# pc2micro.net
KiCad netlist of a schematic drawn in Altium Designer
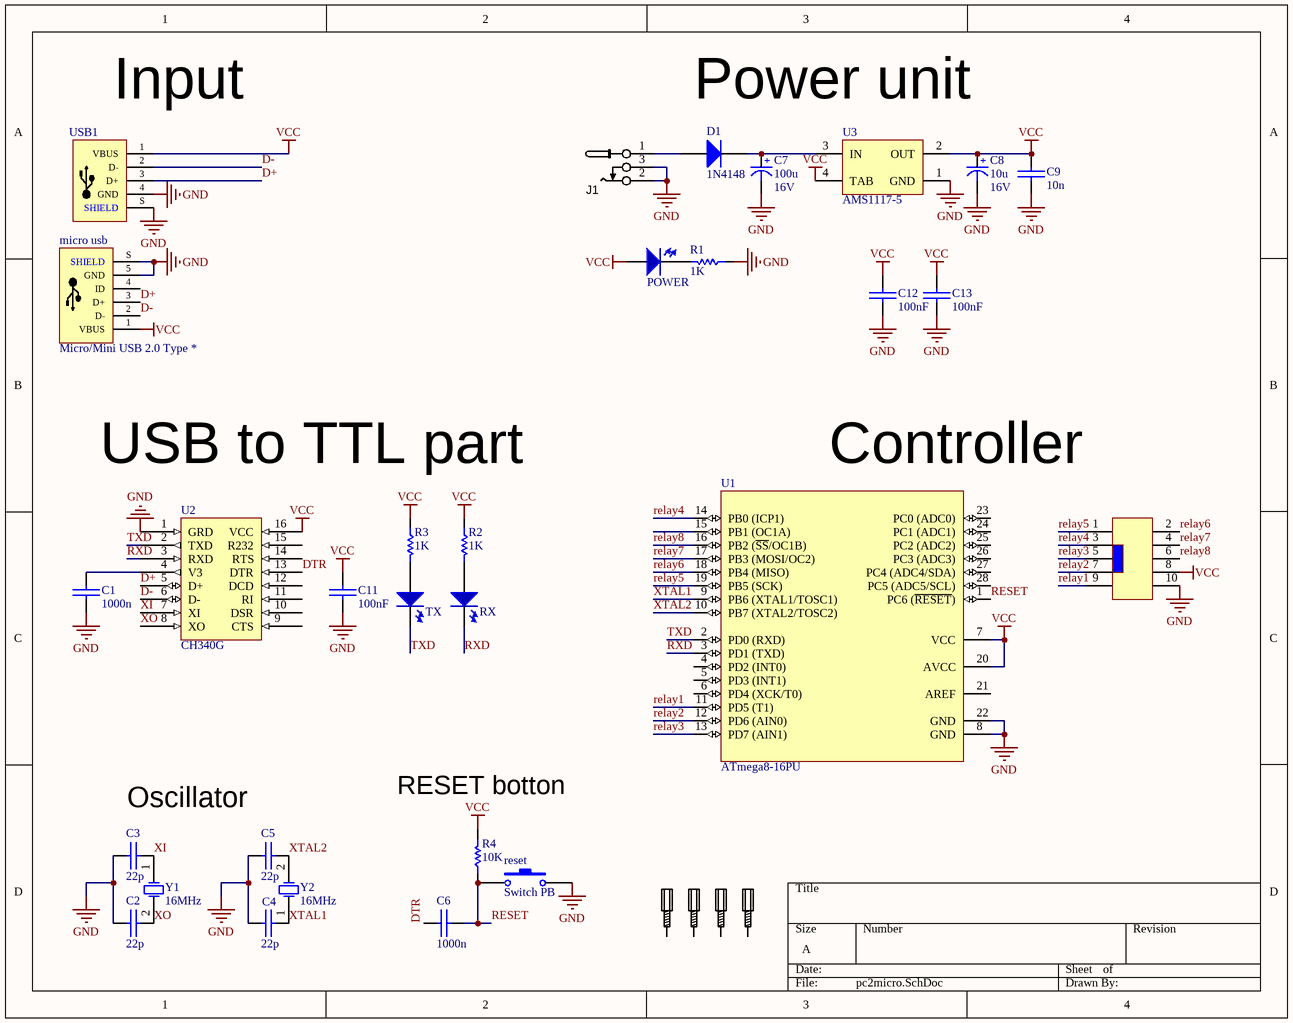
[diagram p0: pc2micro.SchDoc]

(export (version "E")
  (design (tool "Eeschema 10.0.6"))
  (components
    (comp (ref "C1")
      (value "1000n")
      (footprint "Cap - 100nF")
      (description "Bipolar Capacitor")
      (fields (field (name "VOLTAGE") "100V") (field (name "DESIGNER") "Saeid Jorablo"))
      (libsource (lib "My Library") (part "Cap-Bipolar"))
    )
    (comp (ref "C2")
      (value "22p")
      (footprint "Cap - 100nF")
      (description "Bipolar Capacitor")
      (fields (field (name "VOLTAGE") "100V") (field (name "DESIGNER") "Saeid Jorablo"))
      (libsource (lib "My Library") (part "Cap-Bipolar"))
    )
    (comp (ref "C3")
      (value "22p")
      (footprint "Cap - 100nF")
      (description "Bipolar Capacitor")
      (fields (field (name "VOLTAGE") "100V") (field (name "DESIGNER") "Saeid Jorablo"))
      (libsource (lib "My Library") (part "Cap-Bipolar"))
    )
    (comp (ref "C4")
      (value "22p")
      (footprint "Cap - 100nF")
      (description "Bipolar Capacitor")
      (fields (field (name "VOLTAGE") "100V") (field (name "DESIGNER") "Saeid Jorablo"))
      (libsource (lib "My Library") (part "Cap-Bipolar"))
    )
    (comp (ref "C5")
      (value "22p")
      (footprint "Cap - 100nF")
      (description "Bipolar Capacitor")
      (fields (field (name "VOLTAGE") "100V") (field (name "DESIGNER") "Saeid Jorablo"))
      (libsource (lib "My Library") (part "Cap-Bipolar"))
    )
    (comp (ref "C6")
      (value "1000n")
      (footprint "Cap - 100nF")
      (description "Bipolar Capacitor")
      (fields (field (name "VOLTAGE") "100V") (field (name "DESIGNER") "Saeid Jorablo"))
      (libsource (lib "My Library") (part "Cap-Bipolar"))
    )
    (comp (ref "C7")
      (value "100u")
      (footprint "cap 01")
      (description "Polar Capacitor")
      (fields (field (name "VOLTAGE") "16V") (field (name "DESIGNER") "Saeid Jorablo"))
      (libsource (lib "My Library") (part "Cap-Polar"))
    )
    (comp (ref "C8")
      (value "10u")
      (footprint "cap 01")
      (description "Polar Capacitor")
      (fields (field (name "VOLTAGE") "16V") (field (name "DESIGNER") "Saeid Jorablo"))
      (libsource (lib "My Library") (part "Cap-Polar"))
    )
    (comp (ref "C9")
      (value "10n")
      (footprint "Cap - 100nF")
      (description "Bipolar Capacitor")
      (fields (field (name "VOLTAGE") "100V") (field (name "DESIGNER") "Saeid Jorablo"))
      (libsource (lib "My Library") (part "Cap-Bipolar"))
    )
    (comp (ref "C11")
      (value "100nF")
      (footprint "Cap - 100nF")
      (description "Bipolar Capacitor")
      (fields (field (name "VOLTAGE") "100V") (field (name "DESIGNER") "Saeid Jorablo"))
      (libsource (lib "My Library") (part "Cap-Bipolar"))
    )
    (comp (ref "C12")
      (value "100nF")
      (footprint "Cap - 100nF")
      (description "Bipolar Capacitor")
      (fields (field (name "VOLTAGE") "100V") (field (name "DESIGNER") "Saeid Jorablo"))
      (libsource (lib "My Library") (part "Cap-Bipolar"))
    )
    (comp (ref "C13")
      (value "100nF")
      (footprint "Cap - 100nF")
      (description "Bipolar Capacitor")
      (fields (field (name "VOLTAGE") "100V") (field (name "DESIGNER") "Saeid Jorablo"))
      (libsource (lib "My Library") (part "Cap-Bipolar"))
    )
    (comp (ref "D1")
      (value "1N4148")
      (footprint "DO-35")
      (description "High Conductance Fast Diode")
      (fields (field (name "PUBLISHER") "Altium Limited"))
      (libsource (lib "My Library") (part "Diode 1N4148"))
    )
    (comp (ref "IDC1")
      (value "DC3-10")
      (footprint "DC3-2.54-10")
      (description "简易牛角座, 10pins")
      (libsource (lib "AD_Connectors") (part "DC3-10"))
    )
    (comp (ref "J1")
      (value "CONN_PWR_JACK_2.1x5.5mm")
      (footprint "CONN_PWR_JACK_v2")
      (description "Power Connector, THT, 2.1mm ID, 5.5mm OD")
      (fields (field (name "MANUFACTURER") "CUI Inc."))
      (libsource (lib "LimeNet-Micro_2v0") (part "CONN_PWR_JACK_2.1x5.5mm"))
    )
    (comp (ref "MECH1")
      (value "# pcs.")
      (footprint "PCB_standoff")
      (description "STANDOFF M/F MET 5MM HEX 10MM L")
      (fields (field (name "MANUFACTURER") "FIX&FASTEN"))
      (libsource (lib "LimeNet-Micro_2v0") (part "STANDOFF_M-F_THREADED_M3x8x10mm_HEX_5mm dia"))
    )
    (comp (ref "MECH2")
      (value "# pcs.")
      (footprint "PCB_standoff")
      (description "STANDOFF M/F MET 5MM HEX 10MM L")
      (fields (field (name "MANUFACTURER") "FIX&FASTEN"))
      (libsource (lib "LimeNet-Micro_2v0") (part "STANDOFF_M-F_THREADED_M3x8x10mm_HEX_5mm dia"))
    )
    (comp (ref "MECH3")
      (value "# pcs.")
      (footprint "PCB_standoff")
      (description "STANDOFF M/F MET 5MM HEX 10MM L")
      (fields (field (name "MANUFACTURER") "FIX&FASTEN"))
      (libsource (lib "LimeNet-Micro_2v0") (part "STANDOFF_M-F_THREADED_M3x8x10mm_HEX_5mm dia"))
    )
    (comp (ref "MECH4")
      (value "# pcs.")
      (footprint "PCB_standoff")
      (description "STANDOFF M/F MET 5MM HEX 10MM L")
      (fields (field (name "MANUFACTURER") "FIX&FASTEN"))
      (libsource (lib "LimeNet-Micro_2v0") (part "STANDOFF_M-F_THREADED_M3x8x10mm_HEX_5mm dia"))
    )
    (comp (ref "micro usb")
      (value "Micro/Mini USB 2.0 Type *")
      (footprint "Micro_USB2_0_B_SMT_DIP2_1")
      (description "Micro and Mini USB 2.0 (Type A and Type A/B)")
      (libsource (lib "AD_Connectors") (part "USB2_0-Micro&Mini"))
    )
    (comp (ref "POWER")
      (value "SMD LED")
      (footprint "LED 5mm")
      (libsource (lib "ZetaBoard_Lib") (part "LED SMD"))
    )
    (comp (ref "R1")
      (value "1K")
      (footprint "Res-(1/4)")
      (description "Resistor")
      (fields (field (name "TOLERANCE") "5%") (field (name "POWER") "1/8 W"))
      (libsource (lib "My Library") (part "Resistor"))
    )
    (comp (ref "R2")
      (value "1K")
      (footprint "Res-(1/4)")
      (description "Resistor")
      (fields (field (name "TOLERANCE") "5%") (field (name "POWER") "1/8 W"))
      (libsource (lib "My Library") (part "Resistor"))
    )
    (comp (ref "R3")
      (value "1K")
      (footprint "Res-(1/4)")
      (description "Resistor")
      (fields (field (name "TOLERANCE") "5%") (field (name "POWER") "1/8 W"))
      (libsource (lib "My Library") (part "Resistor"))
    )
    (comp (ref "R4")
      (value "10K")
      (footprint "Res-(1/4)")
      (description "Resistor")
      (fields (field (name "TOLERANCE") "5%") (field (name "POWER") "1/8 W"))
      (libsource (lib "My Library") (part "Resistor"))
    )
    (comp (ref "reset")
      (value "Switch PB")
      (footprint "Switch - Push to On")
      (description "Push Button Switch")
      (libsource (lib "My Library") (part "Switch PB"))
    )
    (comp (ref "RX")
      (value "SMD LED")
      (footprint "LED 5mm")
      (libsource (lib "ZetaBoard_Lib") (part "LED SMD"))
    )
    (comp (ref "TX")
      (value "SMD LED")
      (footprint "LED 5mm")
      (libsource (lib "ZetaBoard_Lib") (part "LED SMD"))
    )
    (comp (ref "U1")
      (value "ATmega8-16PU")
      (footprint "28P3")
      (libsource (lib "Atmel Microcontroller megaAVR") (part "ATmega8-16PU"))
    )
    (comp (ref "U2") (value "CH340G") (footprint "SOP-16") (libsource (lib "CH340.Schlib1") (part "CH340G")))
    (comp (ref "U3")
      (value "AMS1117-5")
      (footprint "MP04A_N")
      (description "x.x Volt, 800mA Low-Dropout Linear Regulator, 4-pin SOT-223")
      (fields
        (field (name "PARTNUMBER") "LM1117IMP-3.3")
        (field (name "MANUFACTURER") "National Semiconductor")
        (field (name "PUBLISHER") "Altium Limited")
      )
      (libsource (lib "My Library") (part "LM1117IMP-x.x"))
    )
    (comp (ref "USB1")
      (value "USB 2.0 Type *")
      (footprint "USB2_0_A_DIP")
      (description "USB 2.0 Type A and Type B")
      (fields (field (name "PART NUMBER") "61400413321") (field (name "PUBLISHER") "Wurth Elektronik"))
      (libsource (lib "AD_Connectors") (part "USB2_0-A&B"))
    )
    (comp (ref "Y1")
      (value "16MHz")
      (footprint "XTAL Small")
      (description "XTAL Crystal")
      (libsource (lib "My Library") (part "XTAL"))
    )
    (comp (ref "Y2")
      (value "16MHz")
      (footprint "XTAL Small")
      (description "XTAL Crystal")
      (libsource (lib "My Library") (part "XTAL"))
    )
  )
  (nets
    (net (code "1") (name "/D+") (class "Default")
      (node (ref "U2") (pin "5") (pinfunction "D+_5") (pintype "bidirectional"))
      (node (ref "USB1") (pin "3") (pinfunction "D+_3") (pintype "passive"))
      (node (ref "micro usb") (pin "3") (pinfunction "D+_3") (pintype "passive"))
    )
    (net (code "2") (name "/D-") (class "Default")
      (node (ref "U2") (pin "6") (pinfunction "D-_6") (pintype "bidirectional"))
      (node (ref "USB1") (pin "2") (pinfunction "D-_2") (pintype "passive"))
      (node (ref "micro usb") (pin "2") (pinfunction "D-_2") (pintype "passive"))
    )
    (net (code "3") (name "/DTR") (class "Default")
      (node (ref "C6") (pin "1") (pinfunction "+_1") (pintype "passive"))
      (node (ref "U2") (pin "13") (pinfunction "DTR_13") (pintype "input"))
    )
    (net (code "4") (name "/RESET") (class "Default")
      (node (ref "C6") (pin "2") (pinfunction "-_2") (pintype "passive"))
      (node (ref "R4") (pin "1") (pinfunction "1_1") (pintype "passive"))
      (node (ref "U1") (pin "1") (pinfunction "PC6_(~{RESET})_1") (pintype "bidirectional"))
      (node (ref "reset") (pin "1") (pinfunction "1_1") (pintype "passive"))
    )
    (net (code "5") (name "/RXD") (class "Default")
      (node (ref "RX") (pin "2") (pinfunction "K_2") (pintype "passive"))
      (node (ref "U1") (pin "3") (pinfunction "PD1_(TXD)_3") (pintype "bidirectional"))
      (node (ref "U2") (pin "3") (pinfunction "RXD_3") (pintype "input"))
    )
    (net (code "6") (name "/TXD") (class "Default")
      (node (ref "TX") (pin "2") (pinfunction "K_2") (pintype "passive"))
      (node (ref "U1") (pin "2") (pinfunction "PD0_(RXD)_2") (pintype "bidirectional"))
      (node (ref "U2") (pin "2") (pinfunction "TXD_2") (pintype "output"))
    )
    (net (code "7") (name "/XI") (class "Default")
      (node (ref "C3") (pin "2") (pinfunction "-_2") (pintype "passive"))
      (node (ref "U2") (pin "7") (pinfunction "XI_7") (pintype "input"))
      (node (ref "Y1") (pin "1") (pinfunction "OSC1_1") (pintype "passive"))
    )
    (net (code "8") (name "/XO") (class "Default")
      (node (ref "C2") (pin "2") (pinfunction "-_2") (pintype "passive"))
      (node (ref "U2") (pin "8") (pinfunction "XO_8") (pintype "input"))
      (node (ref "Y1") (pin "2") (pinfunction "OSC2_2") (pintype "passive"))
    )
    (net (code "9") (name "/XTAL1") (class "Default")
      (node (ref "C4") (pin "2") (pinfunction "-_2") (pintype "passive"))
      (node (ref "U1") (pin "9") (pinfunction "PB6_(XTAL1/TOSC1)_9") (pintype "bidirectional"))
      (node (ref "Y2") (pin "1") (pinfunction "OSC1_1") (pintype "passive"))
    )
    (net (code "10") (name "/XTAL2") (class "Default")
      (node (ref "C5") (pin "2") (pinfunction "-_2") (pintype "passive"))
      (node (ref "U1") (pin "10") (pinfunction "PB7_(XTAL2/TOSC2)_10") (pintype "bidirectional"))
      (node (ref "Y2") (pin "2") (pinfunction "OSC2_2") (pintype "passive"))
    )
    (net (code "11") (name "/relay1") (class "Default")
      (node (ref "IDC1") (pin "9") (pinfunction "9_9") (pintype "passive"))
      (node (ref "U1") (pin "11") (pinfunction "PD5_(T1)_11") (pintype "bidirectional"))
    )
    (net (code "12") (name "/relay2") (class "Default")
      (node (ref "IDC1") (pin "7") (pinfunction "7_7") (pintype "passive"))
      (node (ref "U1") (pin "12") (pinfunction "PD6_(AIN0)_12") (pintype "bidirectional"))
    )
    (net (code "13") (name "/relay3") (class "Default")
      (node (ref "IDC1") (pin "5") (pinfunction "5_5") (pintype "passive"))
      (node (ref "U1") (pin "13") (pinfunction "PD7_(AIN1)_13") (pintype "bidirectional"))
    )
    (net (code "14") (name "/relay4") (class "Default")
      (node (ref "IDC1") (pin "3") (pintype "passive"))
      (node (ref "U1") (pin "14") (pinfunction "PB0_(ICP1)_14") (pintype "bidirectional"))
    )
    (net (code "15") (name "/relay5") (class "Default")
      (node (ref "IDC1") (pin "1") (pintype "passive"))
      (node (ref "U1") (pin "19") (pinfunction "PB5_(SCK)_19") (pintype "bidirectional"))
    )
    (net (code "16") (name "/relay6") (class "Default")
      (node (ref "IDC1") (pin "2") (pintype "passive"))
      (node (ref "U1") (pin "18") (pinfunction "PB4_(MISO)_18") (pintype "bidirectional"))
    )
    (net (code "17") (name "/relay7") (class "Default")
      (node (ref "IDC1") (pin "4") (pinfunction "4_4") (pintype "passive"))
      (node (ref "U1") (pin "17") (pinfunction "PB3_(MOSI/OC2)_17") (pintype "bidirectional"))
    )
    (net (code "18") (name "/relay8") (class "Default")
      (node (ref "IDC1") (pin "6") (pinfunction "6_6") (pintype "passive"))
      (node (ref "U1") (pin "16") (pinfunction "PB2_(~{SS}/OC1B)_16") (pintype "bidirectional"))
    )
    (net (code "19") (name "GND") (class "Default")
      (node (ref "C1") (pin "2") (pinfunction "-_2") (pintype "passive"))
      (node (ref "C11") (pin "2") (pinfunction "-_2") (pintype "passive"))
      (node (ref "C12") (pin "2") (pinfunction "-_2") (pintype "passive"))
      (node (ref "C13") (pin "2") (pinfunction "-_2") (pintype "passive"))
      (node (ref "C2") (pin "1") (pinfunction "+_1") (pintype "passive"))
      (node (ref "C3") (pin "1") (pinfunction "+_1") (pintype "passive"))
      (node (ref "C4") (pin "1") (pinfunction "+_1") (pintype "passive"))
      (node (ref "C5") (pin "1") (pinfunction "+_1") (pintype "passive"))
      (node (ref "C7") (pin "2") (pinfunction "-_2") (pintype "passive"))
      (node (ref "C8") (pin "2") (pinfunction "-_2") (pintype "passive"))
      (node (ref "C9") (pin "1") (pinfunction "+_1") (pintype "passive"))
      (node (ref "IDC1") (pin "10") (pinfunction "10_10") (pintype "passive"))
      (node (ref "J1") (pin "2") (pinfunction "2_2") (pintype "passive"))
      (node (ref "J1") (pin "3") (pinfunction "3_3") (pintype "passive"))
      (node (ref "R1") (pin "1") (pinfunction "1_1") (pintype "passive"))
      (node (ref "U1") (pin "22") (pinfunction "GND_22") (pintype "power_in"))
      (node (ref "U1") (pin "8") (pinfunction "GND_8") (pintype "power_in"))
      (node (ref "U2") (pin "1") (pinfunction "GRD_1") (pintype "input"))
      (node (ref "U3") (pin "1") (pinfunction "GND_1") (pintype "power_in"))
      (node (ref "USB1") (pin "4") (pinfunction "GND_4") (pintype "passive"))
      (node (ref "USB1") (pin "S") (pinfunction "SHIELD_S") (pintype "passive"))
      (node (ref "micro usb") (pin "5") (pinfunction "GND_5") (pintype "passive"))
      (node (ref "micro usb") (pin "S") (pinfunction "SHIELD_S") (pintype "passive"))
      (node (ref "reset") (pin "2") (pinfunction "2_2") (pintype "passive"))
    )
    (net (code "20") (name "Net-(C1-+)") (class "Default")
      (node (ref "C1") (pin "1") (pinfunction "+_1") (pintype "passive"))
      (node (ref "U2") (pin "4") (pinfunction "V3_4") (pintype "output"))
    )
    (net (code "21") (name "Net-(C7-+)") (class "Default")
      (node (ref "C7") (pin "1") (pinfunction "+_1") (pintype "passive"))
      (node (ref "D1") (pin "2") (pinfunction "K_2") (pintype "passive"))
      (node (ref "U3") (pin "3") (pinfunction "IN_3") (pintype "power_in"))
    )
    (net (code "22") (name "Net-(D1-A)") (class "Default")
      (node (ref "D1") (pin "1") (pinfunction "A_1") (pintype "passive"))
      (node (ref "J1") (pin "1") (pinfunction "1_1") (pintype "passive"))
    )
    (net (code "23") (name "Net-(POWER-K)") (class "Default")
      (node (ref "POWER") (pin "2") (pinfunction "K_2") (pintype "passive"))
      (node (ref "R1") (pin "2") (pinfunction "2_2") (pintype "passive"))
    )
    (net (code "24") (name "Net-(RX-A)") (class "Default")
      (node (ref "R2") (pin "2") (pinfunction "2_2") (pintype "passive"))
      (node (ref "RX") (pin "1") (pinfunction "A_1") (pintype "passive"))
    )
    (net (code "25") (name "Net-(TX-A)") (class "Default")
      (node (ref "R3") (pin "2") (pinfunction "2_2") (pintype "passive"))
      (node (ref "TX") (pin "1") (pinfunction "A_1") (pintype "passive"))
    )
    (net (code "26") (name "VCC") (class "Default")
      (node (ref "C11") (pin "1") (pinfunction "+_1") (pintype "passive"))
      (node (ref "C12") (pin "1") (pinfunction "+_1") (pintype "passive"))
      (node (ref "C13") (pin "1") (pinfunction "+_1") (pintype "passive"))
      (node (ref "C8") (pin "1") (pinfunction "+_1") (pintype "passive"))
      (node (ref "C9") (pin "2") (pinfunction "-_2") (pintype "passive"))
      (node (ref "IDC1") (pin "8") (pinfunction "8_8") (pintype "passive"))
      (node (ref "POWER") (pin "1") (pinfunction "A_1") (pintype "passive"))
      (node (ref "R2") (pin "1") (pinfunction "1_1") (pintype "passive"))
      (node (ref "R3") (pin "1") (pinfunction "1_1") (pintype "passive"))
      (node (ref "R4") (pin "2") (pinfunction "2_2") (pintype "passive"))
      (node (ref "U1") (pin "20") (pinfunction "AVCC_20") (pintype "power_in"))
      (node (ref "U1") (pin "7") (pinfunction "VCC_7") (pintype "power_in"))
      (node (ref "U2") (pin "16") (pinfunction "VCC_16") (pintype "input"))
      (node (ref "U3") (pin "2") (pinfunction "OUT_2") (pintype "power_in"))
      (node (ref "U3") (pin "4") (pinfunction "TAB_4") (pintype "power_in"))
      (node (ref "USB1") (pin "1") (pinfunction "VBUS_1") (pintype "passive"))
      (node (ref "micro usb") (pin "1") (pinfunction "VBUS_1") (pintype "passive"))
    )
    (net (code "27") (name "unconnected-(MECH1-PadMH1)") (class "Default")
      (node (ref "MECH1") (pin "MH1") (pinfunction "MH1_MH1") (pintype "passive"))
    )
    (net (code "28") (name "unconnected-(MECH2-PadMH1)") (class "Default")
      (node (ref "MECH2") (pin "MH1") (pinfunction "MH1_MH1") (pintype "passive"))
    )
    (net (code "29") (name "unconnected-(MECH3-PadMH1)") (class "Default")
      (node (ref "MECH3") (pin "MH1") (pinfunction "MH1_MH1") (pintype "passive"))
    )
    (net (code "30") (name "unconnected-(MECH4-PadMH1)") (class "Default")
      (node (ref "MECH4") (pin "MH1") (pinfunction "MH1_MH1") (pintype "passive"))
    )
    (net (code "31") (name "unconnected-(U1-AREF-Pad21)") (class "Default")
      (node (ref "U1") (pin "21") (pinfunction "AREF_21") (pintype "passive"))
    )
    (net (code "32") (name "unconnected-(U1-PB1_(OC1A)-Pad15)") (class "Default")
      (node (ref "U1") (pin "15") (pinfunction "PB1_(OC1A)_15") (pintype "bidirectional"))
    )
    (net (code "33") (name "unconnected-(U1-PC0_(ADC0)-Pad23)") (class "Default")
      (node (ref "U1") (pin "23") (pinfunction "PC0_(ADC0)_23") (pintype "bidirectional"))
    )
    (net (code "34") (name "unconnected-(U1-PC1_(ADC1)-Pad24)") (class "Default")
      (node (ref "U1") (pin "24") (pinfunction "PC1_(ADC1)_24") (pintype "bidirectional"))
    )
    (net (code "35") (name "unconnected-(U1-PC2_(ADC2)-Pad25)") (class "Default")
      (node (ref "U1") (pin "25") (pinfunction "PC2_(ADC2)_25") (pintype "bidirectional"))
    )
    (net (code "36") (name "unconnected-(U1-PC3_(ADC3)-Pad26)") (class "Default")
      (node (ref "U1") (pin "26") (pinfunction "PC3_(ADC3)_26") (pintype "bidirectional"))
    )
    (net (code "37") (name "unconnected-(U1-PC4_(ADC4{slash}SDA)-Pad27)") (class "Default")
      (node (ref "U1") (pin "27") (pinfunction "PC4_(ADC4/SDA)_27") (pintype "bidirectional"))
    )
    (net (code "38") (name "unconnected-(U1-PC5_(ADC5{slash}SCL)-Pad28)") (class "Default")
      (node (ref "U1") (pin "28") (pinfunction "PC5_(ADC5/SCL)_28") (pintype "bidirectional"))
    )
    (net (code "39") (name "unconnected-(U1-PD2_(INT0)-Pad4)") (class "Default")
      (node (ref "U1") (pin "4") (pinfunction "PD2_(INT0)_4") (pintype "bidirectional"))
    )
    (net (code "40") (name "unconnected-(U1-PD3_(INT1)-Pad5)") (class "Default")
      (node (ref "U1") (pin "5") (pinfunction "PD3_(INT1)_5") (pintype "bidirectional"))
    )
    (net (code "41") (name "unconnected-(U1-PD4_(XCK{slash}T0)-Pad6)") (class "Default")
      (node (ref "U1") (pin "6") (pinfunction "PD4_(XCK/T0)_6") (pintype "bidirectional"))
    )
    (net (code "42") (name "unconnected-(U2-CTS-Pad9)") (class "Default")
      (node (ref "U2") (pin "9") (pinfunction "CTS_9") (pintype "input"))
    )
    (net (code "43") (name "unconnected-(U2-DCD-Pad12)") (class "Default")
      (node (ref "U2") (pin "12") (pinfunction "DCD_12") (pintype "input"))
    )
    (net (code "44") (name "unconnected-(U2-DSR-Pad10)") (class "Default")
      (node (ref "U2") (pin "10") (pinfunction "DSR_10") (pintype "input"))
    )
    (net (code "45") (name "unconnected-(U2-R232-Pad15)") (class "Default")
      (node (ref "U2") (pin "15") (pinfunction "R232_15") (pintype "input"))
    )
    (net (code "46") (name "unconnected-(U2-RI-Pad11)") (class "Default")
      (node (ref "U2") (pin "11") (pinfunction "RI_11") (pintype "input"))
    )
    (net (code "47") (name "unconnected-(U2-RTS-Pad14)") (class "Default")
      (node (ref "U2") (pin "14") (pinfunction "RTS_14") (pintype "input"))
    )
    (net (code "48") (name "unconnected-(micro usb-ID-Pad4)") (class "Default")
      (node (ref "micro usb") (pin "4") (pinfunction "ID_4") (pintype "passive"))
    )
  )
)
